# sensorline.net
KiCad netlist of a schematic drawn in EAGLE
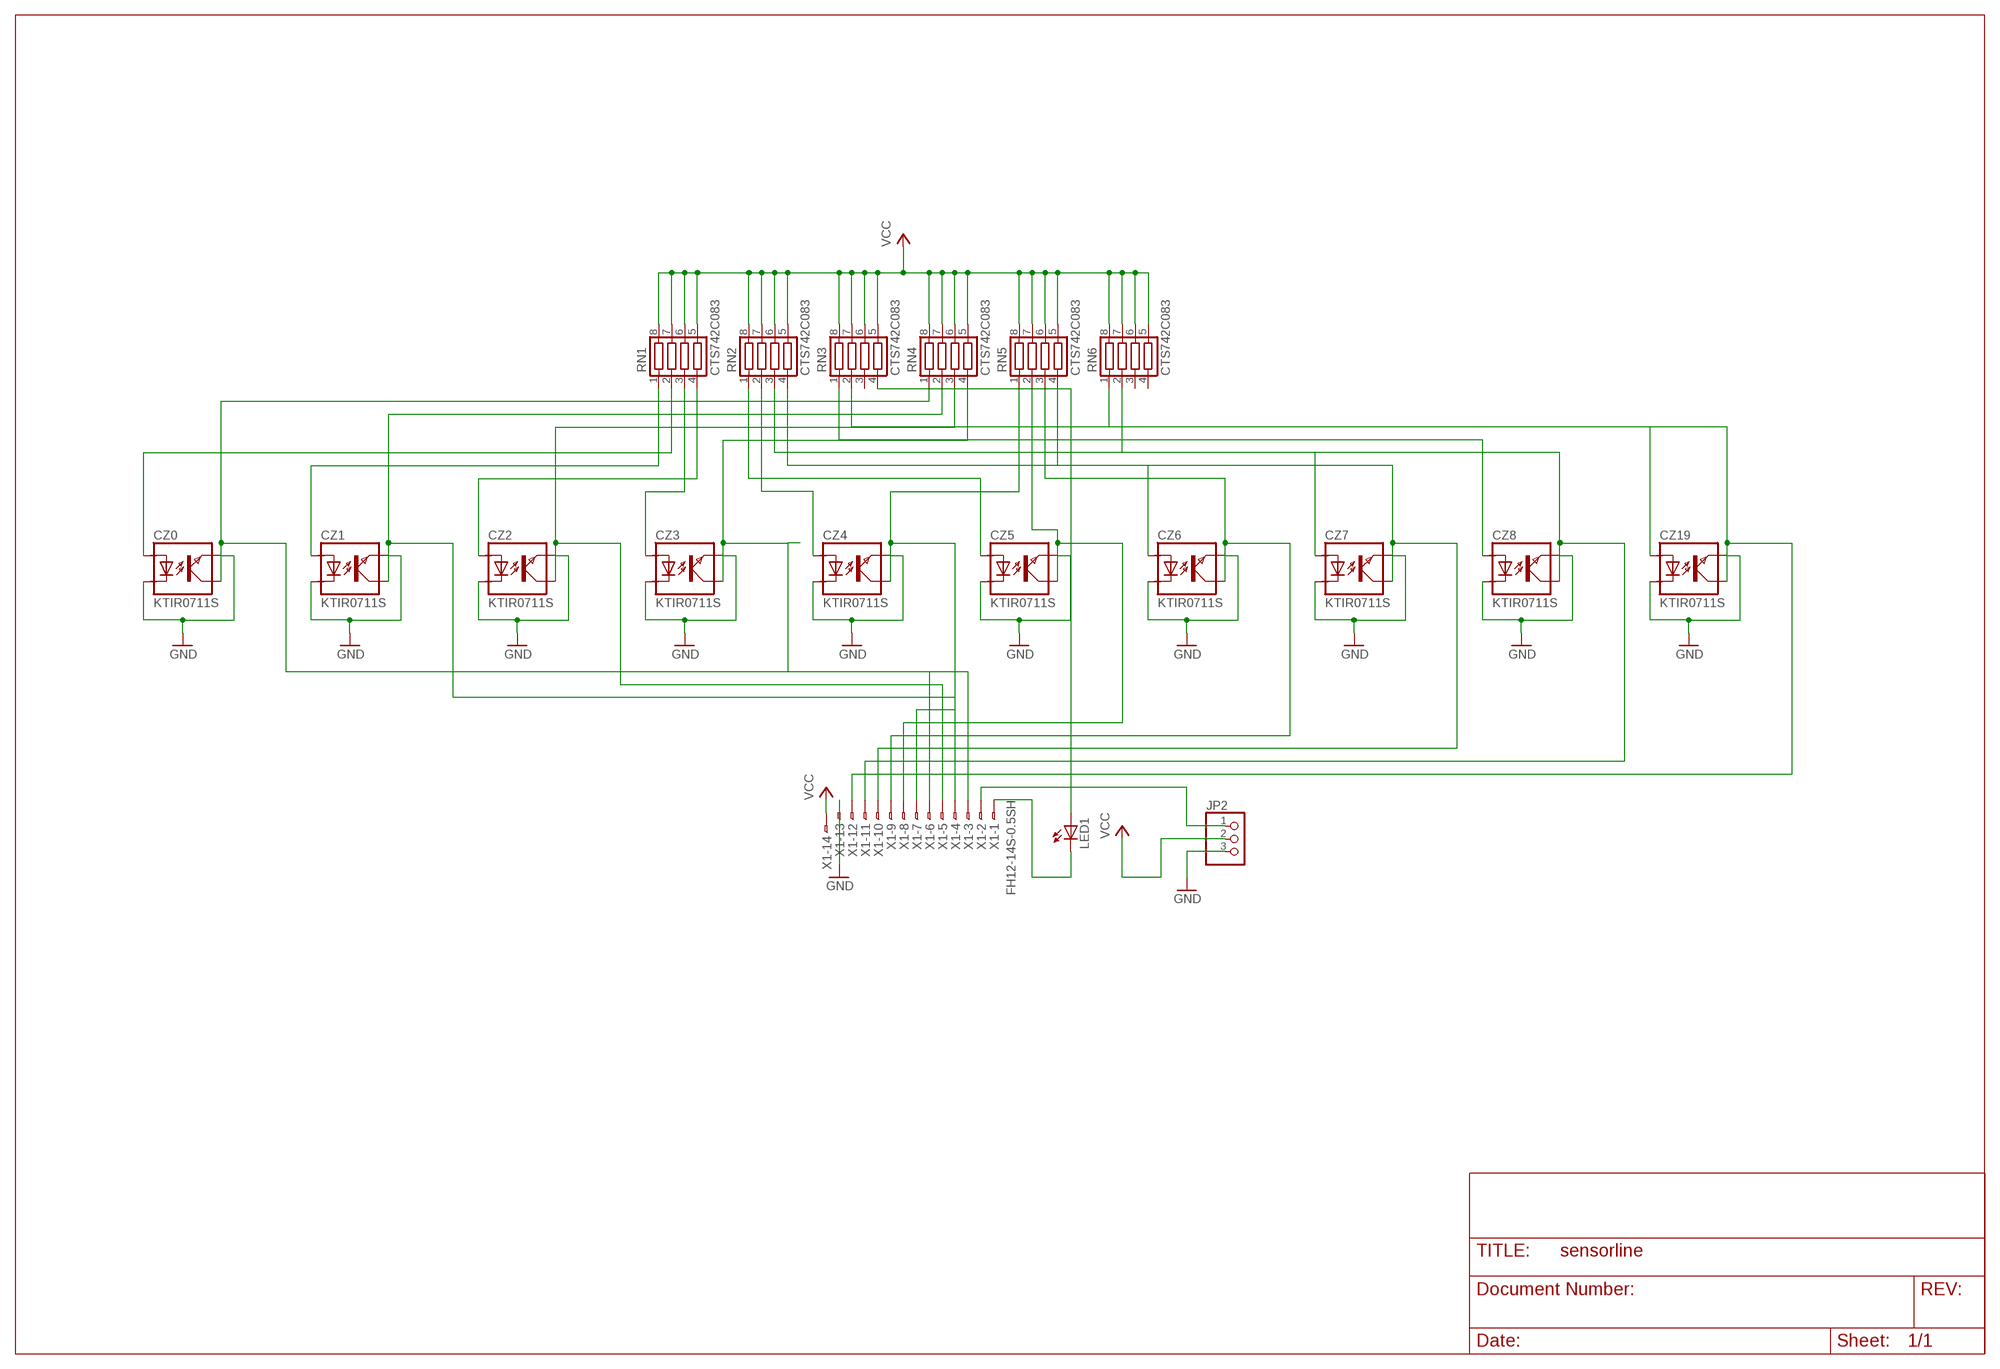
[diagram p0: schematic, sheet 1]

(export (version "E")
  (design (tool "Eeschema 10.0.6"))
  (components
    (comp (ref "CZ0")
      (value "KTIR0711S")
      (footprint "eagle-import:TOP")
      (libsource (lib "eagle-import") (part "KTIR0711S"))
    )
    (comp (ref "CZ1")
      (value "KTIR0711S")
      (footprint "eagle-import:TOP")
      (libsource (lib "eagle-import") (part "KTIR0711S"))
    )
    (comp (ref "CZ2")
      (value "KTIR0711S")
      (footprint "eagle-import:TOP")
      (libsource (lib "eagle-import") (part "KTIR0711S"))
    )
    (comp (ref "CZ3")
      (value "KTIR0711S")
      (footprint "eagle-import:TOP")
      (libsource (lib "eagle-import") (part "KTIR0711S"))
    )
    (comp (ref "CZ4")
      (value "KTIR0711S")
      (footprint "eagle-import:TOP")
      (libsource (lib "eagle-import") (part "KTIR0711S"))
    )
    (comp (ref "CZ5")
      (value "KTIR0711S")
      (footprint "eagle-import:TOP")
      (libsource (lib "eagle-import") (part "KTIR0711S"))
    )
    (comp (ref "CZ6")
      (value "KTIR0711S")
      (footprint "eagle-import:TOP")
      (libsource (lib "eagle-import") (part "KTIR0711S"))
    )
    (comp (ref "CZ7")
      (value "KTIR0711S")
      (footprint "eagle-import:TOP")
      (libsource (lib "eagle-import") (part "KTIR0711S"))
    )
    (comp (ref "CZ8")
      (value "KTIR0711S")
      (footprint "eagle-import:TOP")
      (libsource (lib "eagle-import") (part "KTIR0711S"))
    )
    (comp (ref "CZ19")
      (value "KTIR0711S")
      (footprint "eagle-import:TOP")
      (libsource (lib "eagle-import") (part "KTIR0711S"))
    )
    (comp (ref "JP2")
      (value "PINHD-1X3")
      (footprint "eagle-import:1X03")
      (libsource (lib "eagle-import") (part "PINHD-1X3"))
    )
    (comp (ref "LED1")
      (value "LEDCHIPLED_0603")
      (footprint "eagle-import:CHIPLED_0603")
      (libsource (lib "eagle-import") (part "LEDCHIPLED_0603"))
    )
    (comp (ref "RN1")
      (value "CTS742C083")
      (footprint "eagle-import:CTS742C083")
      (libsource (lib "eagle-import") (part "CTS742C083"))
    )
    (comp (ref "RN2")
      (value "CTS742C083")
      (footprint "eagle-import:CTS742C083")
      (libsource (lib "eagle-import") (part "CTS742C083"))
    )
    (comp (ref "RN3")
      (value "CTS742C083")
      (footprint "eagle-import:CTS742C083")
      (libsource (lib "eagle-import") (part "CTS742C083"))
    )
    (comp (ref "RN4")
      (value "CTS742C083")
      (footprint "eagle-import:CTS742C083")
      (libsource (lib "eagle-import") (part "CTS742C083"))
    )
    (comp (ref "RN5")
      (value "CTS742C083")
      (footprint "eagle-import:CTS742C083")
      (libsource (lib "eagle-import") (part "CTS742C083"))
    )
    (comp (ref "RN6")
      (value "CTS742C083")
      (footprint "eagle-import:CTS742C083")
      (libsource (lib "eagle-import") (part "CTS742C083"))
    )
    (comp (ref "X1")
      (value "FH12-14S-0.5SH")
      (footprint "eagle-import:FH12-14S-0.5SH")
      (fields (field (name "MPN") "MC34827"))
      (libsource (lib "eagle-import") (part "FH12-14S-0.5SH"))
    )
  )
  (nets
    (net (code "1") (name "GND") (class "Default")
      (node (ref "CZ0") (pin "EMITER") (pinfunction "EMITER_EMITER") (pintype "bidirectional"))
      (node (ref "CZ0") (pin "KATODA") (pinfunction "KATODA_KATODA") (pintype "passive"))
      (node (ref "CZ1") (pin "EMITER") (pinfunction "EMITER_EMITER") (pintype "bidirectional"))
      (node (ref "CZ1") (pin "KATODA") (pinfunction "KATODA_KATODA") (pintype "passive"))
      (node (ref "CZ19") (pin "EMITER") (pinfunction "EMITER_EMITER") (pintype "bidirectional"))
      (node (ref "CZ19") (pin "KATODA") (pinfunction "KATODA_KATODA") (pintype "passive"))
      (node (ref "CZ2") (pin "EMITER") (pinfunction "EMITER_EMITER") (pintype "bidirectional"))
      (node (ref "CZ2") (pin "KATODA") (pinfunction "KATODA_KATODA") (pintype "passive"))
      (node (ref "CZ3") (pin "EMITER") (pinfunction "EMITER_EMITER") (pintype "bidirectional"))
      (node (ref "CZ3") (pin "KATODA") (pinfunction "KATODA_KATODA") (pintype "passive"))
      (node (ref "CZ4") (pin "EMITER") (pinfunction "EMITER_EMITER") (pintype "bidirectional"))
      (node (ref "CZ4") (pin "KATODA") (pinfunction "KATODA_KATODA") (pintype "passive"))
      (node (ref "CZ5") (pin "EMITER") (pinfunction "EMITER_EMITER") (pintype "bidirectional"))
      (node (ref "CZ5") (pin "KATODA") (pinfunction "KATODA_KATODA") (pintype "passive"))
      (node (ref "CZ6") (pin "EMITER") (pinfunction "EMITER_EMITER") (pintype "bidirectional"))
      (node (ref "CZ6") (pin "KATODA") (pinfunction "KATODA_KATODA") (pintype "passive"))
      (node (ref "CZ7") (pin "EMITER") (pinfunction "EMITER_EMITER") (pintype "bidirectional"))
      (node (ref "CZ7") (pin "KATODA") (pinfunction "KATODA_KATODA") (pintype "passive"))
      (node (ref "CZ8") (pin "EMITER") (pinfunction "EMITER_EMITER") (pintype "bidirectional"))
      (node (ref "CZ8") (pin "KATODA") (pinfunction "KATODA_KATODA") (pintype "passive"))
      (node (ref "JP2") (pin "3") (pinfunction "3_3") (pintype "passive"))
      (node (ref "X1") (pin "13") (pinfunction "1_13") (pintype "passive"))
    )
    (net (code "2") (name "Net-(CZ0-PadANODA)") (class "Default")
      (node (ref "CZ0") (pin "ANODA") (pinfunction "ANODA_ANODA") (pintype "passive"))
      (node (ref "RN1") (pin "2") (pinfunction "2_2") (pintype "passive"))
    )
    (net (code "3") (name "Net-(CZ1-PadANODA)") (class "Default")
      (node (ref "CZ1") (pin "ANODA") (pinfunction "ANODA_ANODA") (pintype "passive"))
      (node (ref "RN1") (pin "1") (pinfunction "1_1") (pintype "passive"))
    )
    (net (code "4") (name "Net-(CZ2-PadANODA)") (class "Default")
      (node (ref "CZ2") (pin "ANODA") (pinfunction "ANODA_ANODA") (pintype "passive"))
      (node (ref "RN1") (pin "4") (pinfunction "4_4") (pintype "passive"))
    )
    (net (code "5") (name "Net-(CZ3-PadANODA)") (class "Default")
      (node (ref "CZ3") (pin "ANODA") (pinfunction "ANODA_ANODA") (pintype "passive"))
      (node (ref "RN1") (pin "3") (pinfunction "3_3") (pintype "passive"))
    )
    (net (code "6") (name "Net-(CZ4-PadANODA)") (class "Default")
      (node (ref "CZ4") (pin "ANODA") (pinfunction "ANODA_ANODA") (pintype "passive"))
      (node (ref "RN2") (pin "2") (pinfunction "2_2") (pintype "passive"))
    )
    (net (code "7") (name "Net-(CZ5-PadANODA)") (class "Default")
      (node (ref "CZ5") (pin "ANODA") (pinfunction "ANODA_ANODA") (pintype "passive"))
      (node (ref "RN2") (pin "1") (pinfunction "1_1") (pintype "passive"))
    )
    (net (code "8") (name "Net-(CZ6-PadANODA)") (class "Default")
      (node (ref "CZ6") (pin "ANODA") (pinfunction "ANODA_ANODA") (pintype "passive"))
      (node (ref "RN2") (pin "4") (pinfunction "4_4") (pintype "passive"))
    )
    (net (code "9") (name "Net-(CZ7-PadANODA)") (class "Default")
      (node (ref "CZ7") (pin "ANODA") (pinfunction "ANODA_ANODA") (pintype "passive"))
      (node (ref "RN2") (pin "3") (pinfunction "3_3") (pintype "passive"))
    )
    (net (code "10") (name "Net-(CZ8-PadANODA)") (class "Default")
      (node (ref "CZ8") (pin "ANODA") (pinfunction "ANODA_ANODA") (pintype "passive"))
      (node (ref "RN3") (pin "1") (pinfunction "1_1") (pintype "passive"))
    )
    (net (code "11") (name "Net-(CZ19-PadANODA)") (class "Default")
      (node (ref "CZ19") (pin "ANODA") (pinfunction "ANODA_ANODA") (pintype "passive"))
      (node (ref "RN3") (pin "2") (pinfunction "2_2") (pintype "passive"))
    )
    (net (code "12") (name "Net-(LED1-PadA)") (class "Default")
      (node (ref "LED1") (pin "A") (pinfunction "A_A") (pintype "passive"))
      (node (ref "RN3") (pin "4") (pinfunction "4_4") (pintype "passive"))
    )
    (net (code "13") (name "Net-(LED1-PadC)") (class "Default")
      (node (ref "LED1") (pin "C") (pinfunction "C_C") (pintype "passive"))
      (node (ref "X1") (pin "1") (pinfunction "1_1") (pintype "passive"))
    )
    (net (code "14") (name "Net-(X1B-1)") (class "Default")
      (node (ref "CZ7") (pin "KOLEKTOR") (pinfunction "KOLEKTOR_KOLEKTOR") (pintype "bidirectional"))
      (node (ref "RN5") (pin "4") (pinfunction "4_4") (pintype "passive"))
      (node (ref "X1") (pin "10") (pinfunction "1_10") (pintype "passive"))
    )
    (net (code "15") (name "Net-(X1C-1)") (class "Default")
      (node (ref "CZ8") (pin "KOLEKTOR") (pinfunction "KOLEKTOR_KOLEKTOR") (pintype "bidirectional"))
      (node (ref "RN6") (pin "2") (pinfunction "2_2") (pintype "passive"))
      (node (ref "X1") (pin "11") (pinfunction "1_11") (pintype "passive"))
    )
    (net (code "16") (name "Net-(X1D-1)") (class "Default")
      (node (ref "CZ19") (pin "KOLEKTOR") (pinfunction "KOLEKTOR_KOLEKTOR") (pintype "bidirectional"))
      (node (ref "RN6") (pin "1") (pinfunction "1_1") (pintype "passive"))
      (node (ref "X1") (pin "12") (pinfunction "1_12") (pintype "passive"))
    )
    (net (code "17") (name "Net-(X1G-1)") (class "Default")
      (node (ref "JP2") (pin "1") (pinfunction "1_1") (pintype "passive"))
      (node (ref "X1") (pin "2") (pinfunction "1_2") (pintype "passive"))
    )
    (net (code "18") (name "Net-(X1H-1)") (class "Default")
      (node (ref "CZ0") (pin "KOLEKTOR") (pinfunction "KOLEKTOR_KOLEKTOR") (pintype "bidirectional"))
      (node (ref "RN4") (pin "1") (pinfunction "1_1") (pintype "passive"))
      (node (ref "X1") (pin "3") (pinfunction "1_3") (pintype "passive"))
    )
    (net (code "19") (name "Net-(X1I-1)") (class "Default")
      (node (ref "CZ1") (pin "KOLEKTOR") (pinfunction "KOLEKTOR_KOLEKTOR") (pintype "bidirectional"))
      (node (ref "RN4") (pin "2") (pinfunction "2_2") (pintype "passive"))
      (node (ref "X1") (pin "4") (pinfunction "1_4") (pintype "passive"))
    )
    (net (code "20") (name "Net-(X1J-1)") (class "Default")
      (node (ref "CZ2") (pin "KOLEKTOR") (pinfunction "KOLEKTOR_KOLEKTOR") (pintype "bidirectional"))
      (node (ref "RN4") (pin "3") (pinfunction "3_3") (pintype "passive"))
      (node (ref "X1") (pin "5") (pinfunction "1_5") (pintype "passive"))
    )
    (net (code "21") (name "Net-(X1K-1)") (class "Default")
      (node (ref "CZ3") (pin "KOLEKTOR") (pinfunction "KOLEKTOR_KOLEKTOR") (pintype "bidirectional"))
      (node (ref "RN4") (pin "4") (pinfunction "4_4") (pintype "passive"))
      (node (ref "X1") (pin "6") (pinfunction "1_6") (pintype "passive"))
    )
    (net (code "22") (name "Net-(X1L-1)") (class "Default")
      (node (ref "CZ4") (pin "KOLEKTOR") (pinfunction "KOLEKTOR_KOLEKTOR") (pintype "bidirectional"))
      (node (ref "RN5") (pin "1") (pinfunction "1_1") (pintype "passive"))
      (node (ref "X1") (pin "7") (pinfunction "1_7") (pintype "passive"))
    )
    (net (code "23") (name "Net-(X1M-1)") (class "Default")
      (node (ref "CZ5") (pin "KOLEKTOR") (pinfunction "KOLEKTOR_KOLEKTOR") (pintype "bidirectional"))
      (node (ref "RN5") (pin "2") (pinfunction "2_2") (pintype "passive"))
      (node (ref "X1") (pin "8") (pinfunction "1_8") (pintype "passive"))
    )
    (net (code "24") (name "Net-(X1N-1)") (class "Default")
      (node (ref "CZ6") (pin "KOLEKTOR") (pinfunction "KOLEKTOR_KOLEKTOR") (pintype "bidirectional"))
      (node (ref "RN5") (pin "3") (pinfunction "3_3") (pintype "passive"))
      (node (ref "X1") (pin "9") (pinfunction "1_9") (pintype "passive"))
    )
    (net (code "25") (name "VCC") (class "Default")
      (node (ref "JP2") (pin "2") (pinfunction "2_2") (pintype "passive"))
      (node (ref "RN1") (pin "5") (pinfunction "5_5") (pintype "passive"))
      (node (ref "RN1") (pin "6") (pinfunction "6_6") (pintype "passive"))
      (node (ref "RN1") (pin "7") (pinfunction "7_7") (pintype "passive"))
      (node (ref "RN1") (pin "8") (pinfunction "8_8") (pintype "passive"))
      (node (ref "RN2") (pin "5") (pinfunction "5_5") (pintype "passive"))
      (node (ref "RN2") (pin "6") (pinfunction "6_6") (pintype "passive"))
      (node (ref "RN2") (pin "7") (pinfunction "7_7") (pintype "passive"))
      (node (ref "RN2") (pin "8") (pinfunction "8_8") (pintype "passive"))
      (node (ref "RN3") (pin "5") (pinfunction "5_5") (pintype "passive"))
      (node (ref "RN3") (pin "6") (pinfunction "6_6") (pintype "passive"))
      (node (ref "RN3") (pin "7") (pinfunction "7_7") (pintype "passive"))
      (node (ref "RN3") (pin "8") (pinfunction "8_8") (pintype "passive"))
      (node (ref "RN4") (pin "5") (pinfunction "5_5") (pintype "passive"))
      (node (ref "RN4") (pin "6") (pinfunction "6_6") (pintype "passive"))
      (node (ref "RN4") (pin "7") (pinfunction "7_7") (pintype "passive"))
      (node (ref "RN4") (pin "8") (pinfunction "8_8") (pintype "passive"))
      (node (ref "RN5") (pin "5") (pinfunction "5_5") (pintype "passive"))
      (node (ref "RN5") (pin "6") (pinfunction "6_6") (pintype "passive"))
      (node (ref "RN5") (pin "7") (pinfunction "7_7") (pintype "passive"))
      (node (ref "RN5") (pin "8") (pinfunction "8_8") (pintype "passive"))
      (node (ref "RN6") (pin "5") (pinfunction "5_5") (pintype "passive"))
      (node (ref "RN6") (pin "6") (pinfunction "6_6") (pintype "passive"))
      (node (ref "RN6") (pin "7") (pinfunction "7_7") (pintype "passive"))
      (node (ref "RN6") (pin "8") (pinfunction "8_8") (pintype "passive"))
      (node (ref "X1") (pin "14") (pinfunction "1_14") (pintype "passive"))
    )
    (net (code "26") (name "unconnected-(RN3-Pad3)") (class "Default")
      (node (ref "RN3") (pin "3") (pinfunction "3_3") (pintype "passive"))
    )
    (net (code "27") (name "unconnected-(RN6-Pad3)") (class "Default")
      (node (ref "RN6") (pin "3") (pinfunction "3_3") (pintype "passive"))
    )
    (net (code "28") (name "unconnected-(RN6-Pad4)") (class "Default")
      (node (ref "RN6") (pin "4") (pinfunction "4_4") (pintype "passive"))
    )
  )
)
